# RTCC.net
KiCad netlist of a schematic drawn in Altium Designer
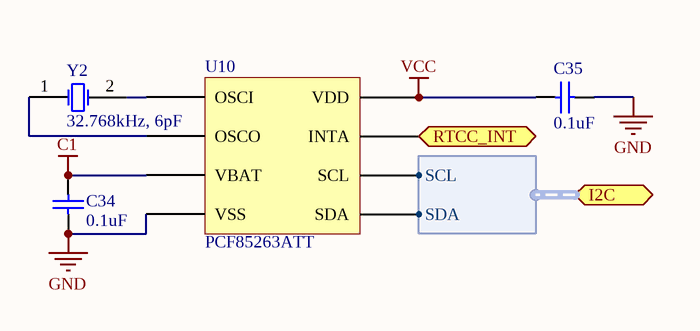
[diagram p0: RTCC.SchDoc]

(export (version "E")
  (design (tool "Eeschema 10.0.6"))
  (components
    (comp (ref "C34")
      (value "0.1uF")
      (footprint "C0402[1005X55]")
      (description "0.1uF 6.3V 10% 0402 (1005 Metric)")
      (fields (field (name "PARTNUMBER") "GRM155R70J104KA01D") (field (name "MANUFACTURER") "Murata"))
      (libsource (lib "Capacitors") (part "CAP_0.1uF_6.3V_0402_10%"))
    )
    (comp (ref "C35")
      (value "0.1uF")
      (footprint "C0402[1005X55]")
      (description "0.1uF 6.3V 10% 0402 (1005 Metric)")
      (fields (field (name "PARTNUMBER") "GRM155R70J104KA01D") (field (name "MANUFACTURER") "Murata"))
      (libsource (lib "Capacitors") (part "CAP_0.1uF_6.3V_0402_10%"))
    )
    (comp (ref "U10")
      (value "PCF85263ATT")
      (footprint "TSSOP-8")
      (description "Real Time Clock Real-Time Clock calendar")
      (fields (field (name "PARTNUMBER") "PCF85263ATT/AJ") (field (name "MANUFACTURER") "Texas Instruments"))
      (libsource (lib "ICs") (part "PCF85263ATT"))
    )
    (comp (ref "Y2")
      (value "32.768kHz, 6pF")
      (footprint "ST3215SB")
      (description "32.768kHz ±20ppm Crystal 6pF 60 kOhm -40°C ~ 85°C Surface Mount 2-SMD, No Lead (DFN, LCC)")
      (fields (field (name "MANUFACTURER") "AVX/Kyocera") (field (name "PARTNUMBER") "ST3215SB32768B0HPWB3"))
      (libsource (lib "Components") (part "ST3215SB32768B0HPWB3"))
    )
  )
  (nets
    (net (code "2") (name "/RTCC_INT") (class "Default")
      (node (ref "U10") (pin "7") (pinfunction "INTA_7") (pintype "passive"))
    )
    (net (code "3") (name "/SCL") (class "Default")
      (node (ref "U10") (pin "6") (pinfunction "SCL_6") (pintype "passive"))
    )
    (net (code "4") (name "/SDA") (class "Default")
      (node (ref "U10") (pin "5") (pinfunction "SDA_5") (pintype "passive"))
    )
    (net (code "6") (name "C1") (class "Default")
      (node (ref "C34") (pin "2") (pinfunction "2_2") (pintype "passive"))
      (node (ref "U10") (pin "3") (pinfunction "VBAT_3") (pintype "power_in"))
    )
    (net (code "7") (name "GND") (class "Default")
      (node (ref "C34") (pin "1") (pinfunction "1_1") (pintype "passive"))
      (node (ref "C35") (pin "2") (pinfunction "2_2") (pintype "passive"))
      (node (ref "U10") (pin "4") (pinfunction "VSS_4") (pintype "power_in"))
    )
    (net (code "8") (name "Net-(U10-OSCI)") (class "Default")
      (node (ref "U10") (pin "1") (pinfunction "OSCI_1") (pintype "passive"))
      (node (ref "Y2") (pin "2") (pinfunction "X2_2") (pintype "passive"))
    )
    (net (code "9") (name "Net-(U10-OSCO)") (class "Default")
      (node (ref "U10") (pin "2") (pinfunction "OSCO_2") (pintype "passive"))
      (node (ref "Y2") (pin "1") (pinfunction "X1_1") (pintype "passive"))
    )
    (net (code "10") (name "VCC") (class "Default")
      (node (ref "C35") (pin "1") (pinfunction "1_1") (pintype "passive"))
      (node (ref "U10") (pin "8") (pinfunction "VDD_8") (pintype "power_in"))
    )
  )
)
